# Limero-ESP01.net
KiCad netlist of a schematic drawn in EAGLE
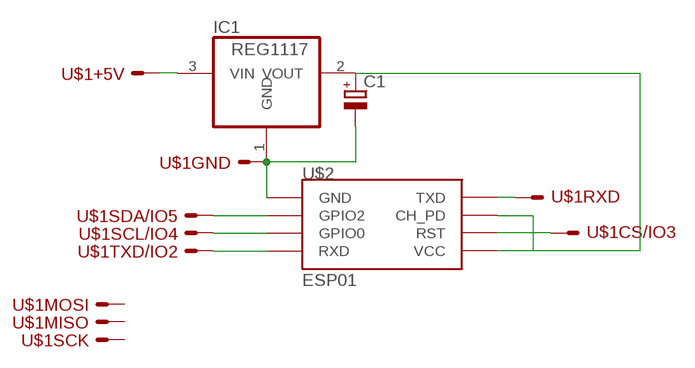
[diagram p0: schematic, sheet 1]

(export (version "E")
  (design (tool "Eeschema 10.0.6"))
  (components
    (comp (ref "C1")
      (value "CPOL-EUB45181A")
      (footprint "eagle-import:B45181A")
      (libsource (lib "eagle-import") (part "CPOL-EUB45181A"))
    )
    (comp (ref "IC1")
      (value "REG1117")
      (footprint "eagle-import:SOT223")
      (libsource (lib "eagle-import") (part "REG1117"))
    )
    (comp (ref "U$1")
      (value "LIMERO_BUS")
      (footprint "eagle-import:SPI_BUS")
      (libsource (lib "eagle-import") (part "LIMERO_BUS"))
    )
    (comp (ref "U$2")
      (value "ESP01")
      (footprint "eagle-import:ESP01")
      (libsource (lib "eagle-import") (part "ESP01"))
    )
  )
  (nets
    (net (code "1") (name "Net-(IC1-GND)") (class "Default")
      (node (ref "C1") (pin "-") (pinfunction "-_-") (pintype "passive"))
      (node (ref "IC1") (pin "1") (pinfunction "GND_1") (pintype "power_in"))
      (node (ref "U$1") (pin "GND") (pinfunction "S_GND") (pintype "passive"))
      (node (ref "U$2") (pin "GND") (pinfunction "GND_GND") (pintype "bidirectional"))
    )
    (net (code "2") (name "Net-(IC1-VIN)") (class "Default")
      (node (ref "IC1") (pin "3") (pinfunction "VIN_3") (pintype "input"))
      (node (ref "U$1") (pin "+5V") (pinfunction "S_+5V") (pintype "passive"))
    )
    (net (code "3") (name "Net-(IC1-VOUT)") (class "Default")
      (node (ref "C1") (pin "+") (pinfunction "+_+") (pintype "passive"))
      (node (ref "IC1") (pin "2") (pinfunction "VOUT_2") (pintype "output"))
      (node (ref "U$2") (pin "CH_PD") (pinfunction "CH_PD_CH_PD") (pintype "bidirectional"))
      (node (ref "U$2") (pin "VCC") (pinfunction "VCC_VCC") (pintype "bidirectional"))
    )
    (net (code "4") (name "Net-(U$1B-S)") (class "Default")
      (node (ref "U$1") (pin "CS") (pinfunction "S_CS") (pintype "passive"))
      (node (ref "U$2") (pin "RST") (pinfunction "RST_RST") (pintype "bidirectional"))
    )
    (net (code "5") (name "Net-(U$1F-S)") (class "Default")
      (node (ref "U$1") (pin "RXD") (pinfunction "S_RXD") (pintype "passive"))
      (node (ref "U$2") (pin "TX") (pinfunction "TXD_TX") (pintype "bidirectional"))
    )
    (net (code "6") (name "Net-(U$1H-S)") (class "Default")
      (node (ref "U$1") (pin "SCL") (pinfunction "S_SCL") (pintype "passive"))
      (node (ref "U$2") (pin "GPIO0") (pinfunction "GPIO0_GPIO0") (pintype "bidirectional"))
    )
    (net (code "7") (name "Net-(U$1I-S)") (class "Default")
      (node (ref "U$1") (pin "SDA") (pinfunction "S_SDA") (pintype "passive"))
      (node (ref "U$2") (pin "GPIO2") (pinfunction "GPIO2_GPIO2") (pintype "bidirectional"))
    )
    (net (code "8") (name "Net-(U$1J-S)") (class "Default")
      (node (ref "U$1") (pin "TXD") (pinfunction "S_TXD") (pintype "passive"))
      (node (ref "U$2") (pin "RX") (pinfunction "RXD_RX") (pintype "bidirectional"))
    )
    (net (code "9") (name "unconnected-(U$1D-S-PadMISO)") (class "Default")
      (node (ref "U$1") (pin "MISO") (pinfunction "S_MISO") (pintype "passive"))
    )
    (net (code "10") (name "unconnected-(U$1E-S-PadMOSI)") (class "Default")
      (node (ref "U$1") (pin "MOSI") (pinfunction "S_MOSI") (pintype "passive"))
    )
    (net (code "11") (name "unconnected-(U$1G-S-PadSCK)") (class "Default")
      (node (ref "U$1") (pin "SCK") (pinfunction "S_SCK") (pintype "passive"))
    )
  )
)
